# magic-donut.net
KiCad netlist of a schematic drawn in EAGLE
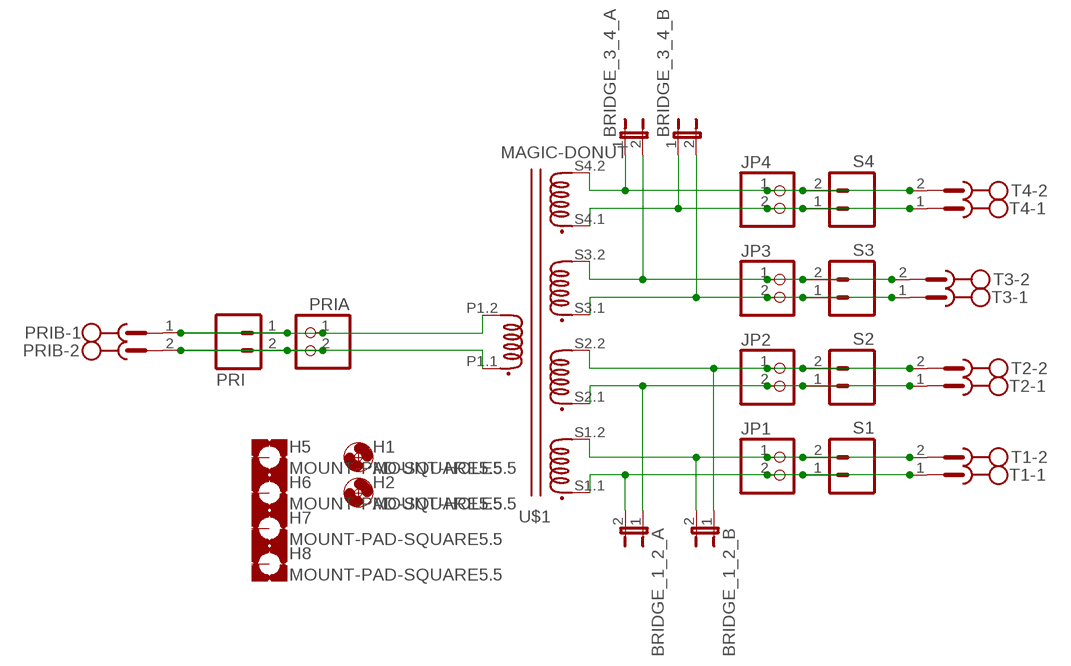
[diagram p0: schematic, sheet 1]

(export (version "E")
  (design (tool "Eeschema 10.0.6"))
  (components
    (comp (ref "BRIDGE_1_2_A")
      (value "JP1E")
      (footprint "eagle-import:JP1")
      (libsource (lib "eagle-import") (part "JP1E"))
    )
    (comp (ref "BRIDGE_1_2_B")
      (value "JP1E")
      (footprint "eagle-import:JP1")
      (libsource (lib "eagle-import") (part "JP1E"))
    )
    (comp (ref "BRIDGE_3_4_A")
      (value "JP1E")
      (footprint "eagle-import:JP1")
      (libsource (lib "eagle-import") (part "JP1E"))
    )
    (comp (ref "BRIDGE_3_4_B")
      (value "JP1E")
      (footprint "eagle-import:JP1")
      (libsource (lib "eagle-import") (part "JP1E"))
    )
    (comp (ref "H1")
      (value "MOUNT-HOLE5.5")
      (footprint "eagle-import:5,5")
      (libsource (lib "eagle-import") (part "MOUNT-HOLE5.5"))
    )
    (comp (ref "H2")
      (value "MOUNT-HOLE5.5")
      (footprint "eagle-import:5,5")
      (libsource (lib "eagle-import") (part "MOUNT-HOLE5.5"))
    )
    (comp (ref "H5")
      (value "MOUNT-PAD-SQUARE5.5")
      (footprint "eagle-import:5,5-PAD-SQUARE")
      (libsource (lib "eagle-import") (part "MOUNT-PAD-SQUARE5.5"))
    )
    (comp (ref "H6")
      (value "MOUNT-PAD-SQUARE5.5")
      (footprint "eagle-import:5,5-PAD-SQUARE")
      (libsource (lib "eagle-import") (part "MOUNT-PAD-SQUARE5.5"))
    )
    (comp (ref "H7")
      (value "MOUNT-PAD-SQUARE5.5")
      (footprint "eagle-import:5,5-PAD-SQUARE")
      (libsource (lib "eagle-import") (part "MOUNT-PAD-SQUARE5.5"))
    )
    (comp (ref "H8")
      (value "MOUNT-PAD-SQUARE5.5")
      (footprint "eagle-import:5,5-PAD-SQUARE")
      (libsource (lib "eagle-import") (part "MOUNT-PAD-SQUARE5.5"))
    )
    (comp (ref "JP1")
      (value "PINHD-1X2")
      (footprint "eagle-import:1X02")
      (libsource (lib "eagle-import") (part "PINHD-1X2"))
    )
    (comp (ref "JP2")
      (value "PINHD-1X2")
      (footprint "eagle-import:1X02")
      (libsource (lib "eagle-import") (part "PINHD-1X2"))
    )
    (comp (ref "JP3")
      (value "PINHD-1X2")
      (footprint "eagle-import:1X02")
      (libsource (lib "eagle-import") (part "PINHD-1X2"))
    )
    (comp (ref "JP4")
      (value "PINHD-1X2")
      (footprint "eagle-import:1X02")
      (libsource (lib "eagle-import") (part "PINHD-1X2"))
    )
    (comp (ref "PRI")
      (value "M02JST-PTH-2")
      (footprint "eagle-import:JST-2-PTH")
      (libsource (lib "eagle-import") (part "M02JST-PTH-2"))
    )
    (comp (ref "PRIA")
      (value "PINHD-1X2")
      (footprint "eagle-import:1X02")
      (libsource (lib "eagle-import") (part "PINHD-1X2"))
    )
    (comp (ref "PRIB")
      (value "MSTBV2")
      (footprint "eagle-import:MSTBV2")
      (libsource (lib "eagle-import") (part "MSTBV2"))
    )
    (comp (ref "S1")
      (value "M02JST-PTH-2")
      (footprint "eagle-import:JST-2-PTH")
      (libsource (lib "eagle-import") (part "M02JST-PTH-2"))
    )
    (comp (ref "S2")
      (value "M02JST-PTH-2")
      (footprint "eagle-import:JST-2-PTH")
      (libsource (lib "eagle-import") (part "M02JST-PTH-2"))
    )
    (comp (ref "S3")
      (value "M02JST-PTH-2")
      (footprint "eagle-import:JST-2-PTH")
      (libsource (lib "eagle-import") (part "M02JST-PTH-2"))
    )
    (comp (ref "S4")
      (value "M02JST-PTH-2")
      (footprint "eagle-import:JST-2-PTH")
      (libsource (lib "eagle-import") (part "M02JST-PTH-2"))
    )
    (comp (ref "T1")
      (value "MSTBV2")
      (footprint "eagle-import:MSTBV2")
      (libsource (lib "eagle-import") (part "MSTBV2"))
    )
    (comp (ref "T2")
      (value "MSTBV2")
      (footprint "eagle-import:MSTBV2")
      (libsource (lib "eagle-import") (part "MSTBV2"))
    )
    (comp (ref "T3")
      (value "MSTBV2")
      (footprint "eagle-import:MSTBV2")
      (libsource (lib "eagle-import") (part "MSTBV2"))
    )
    (comp (ref "T4")
      (value "MSTBV2")
      (footprint "eagle-import:MSTBV2")
      (libsource (lib "eagle-import") (part "MSTBV2"))
    )
    (comp (ref "U$1")
      (value "MAGIC-DONUT")
      (footprint "eagle-import:TOROID")
      (libsource (lib "eagle-import") (part "MAGIC-DONUT"))
    )
  )
  (nets
    (net (code "1") (name "Net-(PRIBA-SK)") (class "Default")
      (node (ref "PRI") (pin "1") (pinfunction "1_1") (pintype "passive"))
      (node (ref "PRIA") (pin "1") (pinfunction "1_1") (pintype "passive"))
      (node (ref "PRIB") (pin "1") (pinfunction "SK_1") (pintype "passive"))
      (node (ref "U$1") (pin "P1.2") (pinfunction "P1.2_P1.2") (pintype "passive"))
    )
    (net (code "2") (name "Net-(PRIBB-SK)") (class "Default")
      (node (ref "PRI") (pin "2") (pinfunction "2_2") (pintype "passive"))
      (node (ref "PRIA") (pin "2") (pinfunction "2_2") (pintype "passive"))
      (node (ref "PRIB") (pin "2") (pinfunction "SK_2") (pintype "passive"))
      (node (ref "U$1") (pin "P1.1") (pinfunction "P1.1_P1.1") (pintype "passive"))
    )
    (net (code "3") (name "Net-(T1A-SK)") (class "Default")
      (node (ref "BRIDGE_1_2_A") (pin "2") (pinfunction "2_2") (pintype "passive"))
      (node (ref "JP1") (pin "2") (pinfunction "2_2") (pintype "passive"))
      (node (ref "S1") (pin "1") (pinfunction "1_1") (pintype "passive"))
      (node (ref "T1") (pin "1") (pinfunction "SK_1") (pintype "passive"))
      (node (ref "U$1") (pin "S1.1") (pinfunction "S1.1_S1.1") (pintype "passive"))
    )
    (net (code "4") (name "Net-(T1B-SK)") (class "Default")
      (node (ref "BRIDGE_1_2_B") (pin "2") (pinfunction "2_2") (pintype "passive"))
      (node (ref "JP1") (pin "1") (pinfunction "1_1") (pintype "passive"))
      (node (ref "S1") (pin "2") (pinfunction "2_2") (pintype "passive"))
      (node (ref "T1") (pin "2") (pinfunction "SK_2") (pintype "passive"))
      (node (ref "U$1") (pin "S1.2") (pinfunction "S1.2_S1.2") (pintype "passive"))
    )
    (net (code "5") (name "Net-(T2A-SK)") (class "Default")
      (node (ref "BRIDGE_1_2_A") (pin "1") (pinfunction "1_1") (pintype "passive"))
      (node (ref "JP2") (pin "2") (pinfunction "2_2") (pintype "passive"))
      (node (ref "S2") (pin "1") (pinfunction "1_1") (pintype "passive"))
      (node (ref "T2") (pin "1") (pinfunction "SK_1") (pintype "passive"))
      (node (ref "U$1") (pin "S2.1") (pinfunction "S2.1_S2.1") (pintype "passive"))
    )
    (net (code "6") (name "Net-(T2B-SK)") (class "Default")
      (node (ref "BRIDGE_1_2_B") (pin "1") (pinfunction "1_1") (pintype "passive"))
      (node (ref "JP2") (pin "1") (pinfunction "1_1") (pintype "passive"))
      (node (ref "S2") (pin "2") (pinfunction "2_2") (pintype "passive"))
      (node (ref "T2") (pin "2") (pinfunction "SK_2") (pintype "passive"))
      (node (ref "U$1") (pin "S2.2") (pinfunction "S2.2_S2.2") (pintype "passive"))
    )
    (net (code "7") (name "Net-(T3A-SK)") (class "Default")
      (node (ref "BRIDGE_3_4_B") (pin "2") (pinfunction "2_2") (pintype "passive"))
      (node (ref "JP3") (pin "2") (pinfunction "2_2") (pintype "passive"))
      (node (ref "S3") (pin "1") (pinfunction "1_1") (pintype "passive"))
      (node (ref "T3") (pin "1") (pinfunction "SK_1") (pintype "passive"))
      (node (ref "U$1") (pin "S3.1") (pinfunction "S3.1_S3.1") (pintype "passive"))
    )
    (net (code "8") (name "Net-(T3B-SK)") (class "Default")
      (node (ref "BRIDGE_3_4_A") (pin "2") (pinfunction "2_2") (pintype "passive"))
      (node (ref "JP3") (pin "1") (pinfunction "1_1") (pintype "passive"))
      (node (ref "S3") (pin "2") (pinfunction "2_2") (pintype "passive"))
      (node (ref "T3") (pin "2") (pinfunction "SK_2") (pintype "passive"))
      (node (ref "U$1") (pin "S3.2") (pinfunction "S3.2_S3.2") (pintype "passive"))
    )
    (net (code "9") (name "Net-(T4A-SK)") (class "Default")
      (node (ref "BRIDGE_3_4_B") (pin "1") (pinfunction "1_1") (pintype "passive"))
      (node (ref "JP4") (pin "2") (pinfunction "2_2") (pintype "passive"))
      (node (ref "S4") (pin "1") (pinfunction "1_1") (pintype "passive"))
      (node (ref "T4") (pin "1") (pinfunction "SK_1") (pintype "passive"))
      (node (ref "U$1") (pin "S4.1") (pinfunction "S4.1_S4.1") (pintype "passive"))
    )
    (net (code "10") (name "Net-(T4B-SK)") (class "Default")
      (node (ref "BRIDGE_3_4_A") (pin "1") (pinfunction "1_1") (pintype "passive"))
      (node (ref "JP4") (pin "1") (pinfunction "1_1") (pintype "passive"))
      (node (ref "S4") (pin "2") (pinfunction "2_2") (pintype "passive"))
      (node (ref "T4") (pin "2") (pinfunction "SK_2") (pintype "passive"))
      (node (ref "U$1") (pin "S4.2") (pinfunction "S4.2_S4.2") (pintype "passive"))
    )
    (net (code "11") (name "unconnected-(H5-MOUNT-PadB5,5)") (class "Default")
      (node (ref "H5") (pin "B5,5") (pinfunction "MOUNT_B5,5") (pintype "passive"))
    )
    (net (code "12") (name "unconnected-(H6-MOUNT-PadB5,5)") (class "Default")
      (node (ref "H6") (pin "B5,5") (pinfunction "MOUNT_B5,5") (pintype "passive"))
    )
    (net (code "13") (name "unconnected-(H7-MOUNT-PadB5,5)") (class "Default")
      (node (ref "H7") (pin "B5,5") (pinfunction "MOUNT_B5,5") (pintype "passive"))
    )
    (net (code "14") (name "unconnected-(H8-MOUNT-PadB5,5)") (class "Default")
      (node (ref "H8") (pin "B5,5") (pinfunction "MOUNT_B5,5") (pintype "passive"))
    )
  )
)
